# MainBoard.net
KiCad netlist of a schematic drawn in EAGLE
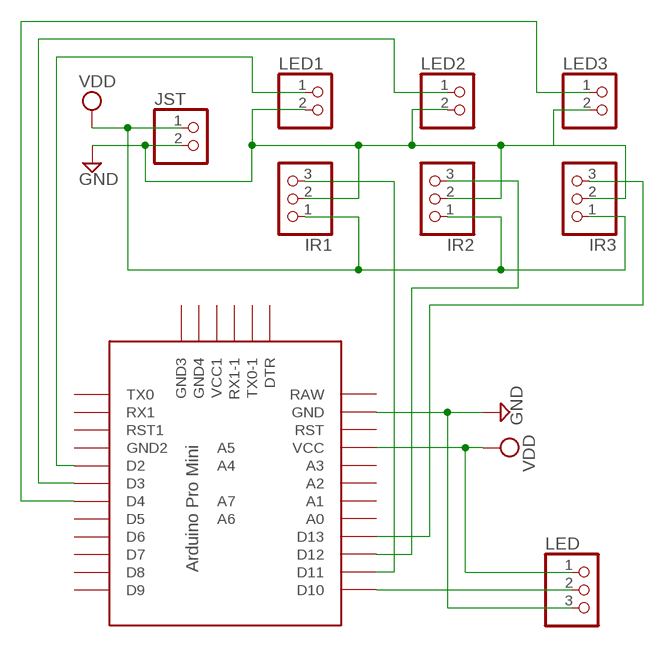
[diagram p0: schematic, sheet 1]

(export (version "E")
  (design (tool "Eeschema 10.0.6"))
  (components
    (comp (ref "IR1")
      (value "PINHD-1X3")
      (footprint "eagle-import:1X03")
      (libsource (lib "eagle-import") (part "PINHD-1X3"))
    )
    (comp (ref "IR2")
      (value "PINHD-1X3")
      (footprint "eagle-import:1X03")
      (libsource (lib "eagle-import") (part "PINHD-1X3"))
    )
    (comp (ref "IR3")
      (value "PINHD-1X3")
      (footprint "eagle-import:1X03")
      (libsource (lib "eagle-import") (part "PINHD-1X3"))
    )
    (comp (ref "JST")
      (value "PINHD-1X2/90")
      (footprint "eagle-import:1X02_90")
      (libsource (lib "eagle-import") (part "PINHD-1X2/90"))
    )
    (comp (ref "LED")
      (value "PINHD-1X3")
      (footprint "eagle-import:1X03")
      (libsource (lib "eagle-import") (part "PINHD-1X3"))
    )
    (comp (ref "LED1")
      (value "PINHD-1X2")
      (footprint "eagle-import:1X02")
      (libsource (lib "eagle-import") (part "PINHD-1X2"))
    )
    (comp (ref "LED2")
      (value "PINHD-1X2")
      (footprint "eagle-import:1X02")
      (libsource (lib "eagle-import") (part "PINHD-1X2"))
    )
    (comp (ref "LED3")
      (value "PINHD-1X2")
      (footprint "eagle-import:1X02")
      (libsource (lib "eagle-import") (part "PINHD-1X2"))
    )
    (comp (ref "U$1")
      (value "PRO-MINI-2")
      (footprint "eagle-import:PRO-MINI-2")
      (libsource (lib "eagle-import") (part "PRO-MINI-2"))
    )
  )
  (nets
    (net (code "1") (name "GND") (class "Default")
      (node (ref "IR1") (pin "2") (pinfunction "2_2") (pintype "passive"))
      (node (ref "IR2") (pin "2") (pinfunction "2_2") (pintype "passive"))
      (node (ref "IR3") (pin "2") (pinfunction "2_2") (pintype "passive"))
      (node (ref "JST") (pin "2") (pinfunction "2_2") (pintype "passive"))
      (node (ref "LED") (pin "3") (pinfunction "3_3") (pintype "passive"))
      (node (ref "LED1") (pin "2") (pinfunction "2_2") (pintype "passive"))
      (node (ref "LED2") (pin "2") (pinfunction "2_2") (pintype "passive"))
      (node (ref "LED3") (pin "2") (pinfunction "2_2") (pintype "passive"))
      (node (ref "U$1") (pin "GND") (pinfunction "GND_GND") (pintype "bidirectional"))
    )
    (net (code "2") (name "Net-(IR1-Pad3)") (class "Default")
      (node (ref "IR1") (pin "3") (pinfunction "3_3") (pintype "passive"))
      (node (ref "U$1") (pin "D11") (pinfunction "D11_D11") (pintype "bidirectional"))
    )
    (net (code "3") (name "Net-(IR2-Pad3)") (class "Default")
      (node (ref "IR2") (pin "3") (pinfunction "3_3") (pintype "passive"))
      (node (ref "U$1") (pin "D12") (pinfunction "D12_D12") (pintype "bidirectional"))
    )
    (net (code "4") (name "Net-(IR3-Pad3)") (class "Default")
      (node (ref "IR3") (pin "3") (pinfunction "3_3") (pintype "passive"))
      (node (ref "U$1") (pin "D13") (pinfunction "D13_D13") (pintype "bidirectional"))
    )
    (net (code "5") (name "Net-(LED-Pad2)") (class "Default")
      (node (ref "LED") (pin "2") (pinfunction "2_2") (pintype "passive"))
      (node (ref "U$1") (pin "D10") (pinfunction "D10_D10") (pintype "bidirectional"))
    )
    (net (code "6") (name "Net-(LED1-Pad1)") (class "Default")
      (node (ref "LED1") (pin "1") (pinfunction "1_1") (pintype "passive"))
      (node (ref "U$1") (pin "D2") (pinfunction "D2_D2") (pintype "bidirectional"))
    )
    (net (code "7") (name "Net-(LED2-Pad1)") (class "Default")
      (node (ref "LED2") (pin "1") (pinfunction "1_1") (pintype "passive"))
      (node (ref "U$1") (pin "D3") (pinfunction "D3_D3") (pintype "bidirectional"))
    )
    (net (code "8") (name "Net-(LED3-Pad1)") (class "Default")
      (node (ref "LED3") (pin "1") (pinfunction "1_1") (pintype "passive"))
      (node (ref "U$1") (pin "D4") (pinfunction "D4_D4") (pintype "bidirectional"))
    )
    (net (code "9") (name "VDD") (class "Default")
      (node (ref "IR1") (pin "1") (pinfunction "1_1") (pintype "passive"))
      (node (ref "IR2") (pin "1") (pinfunction "1_1") (pintype "passive"))
      (node (ref "IR3") (pin "1") (pinfunction "1_1") (pintype "passive"))
      (node (ref "JST") (pin "1") (pinfunction "1_1") (pintype "passive"))
      (node (ref "LED") (pin "1") (pinfunction "1_1") (pintype "passive"))
      (node (ref "U$1") (pin "VCC") (pinfunction "VCC_VCC") (pintype "bidirectional"))
    )
    (net (code "10") (name "unconnected-(U$1-GND2-PadGND1)") (class "Default")
      (node (ref "U$1") (pin "GND1") (pinfunction "GND2_GND1") (pintype "bidirectional"))
    )
    (net (code "11") (name "unconnected-(U$1-GND3-PadGND2)") (class "Default")
      (node (ref "U$1") (pin "GND2") (pinfunction "GND3_GND2") (pintype "bidirectional"))
    )
    (net (code "12") (name "unconnected-(U$1-GND4-PadGND3)") (class "Default")
      (node (ref "U$1") (pin "GND3") (pinfunction "GND4_GND3") (pintype "bidirectional"))
    )
    (net (code "13") (name "unconnected-(U$1-PadA0)") (class "Default")
      (node (ref "U$1") (pin "A0") (pinfunction "A0_A0") (pintype "bidirectional"))
    )
    (net (code "14") (name "unconnected-(U$1-PadA1)") (class "Default")
      (node (ref "U$1") (pin "A1") (pinfunction "A1_A1") (pintype "bidirectional"))
    )
    (net (code "15") (name "unconnected-(U$1-PadA2)") (class "Default")
      (node (ref "U$1") (pin "A2") (pinfunction "A2_A2") (pintype "bidirectional"))
    )
    (net (code "16") (name "unconnected-(U$1-PadA3)") (class "Default")
      (node (ref "U$1") (pin "A3") (pinfunction "A3_A3") (pintype "bidirectional"))
    )
    (net (code "17") (name "unconnected-(U$1-PadA4)") (class "Default")
      (node (ref "U$1") (pin "A4") (pinfunction "A4_A4") (pintype "bidirectional"))
    )
    (net (code "18") (name "unconnected-(U$1-PadA5)") (class "Default")
      (node (ref "U$1") (pin "A5") (pinfunction "A5_A5") (pintype "bidirectional"))
    )
    (net (code "19") (name "unconnected-(U$1-PadA6)") (class "Default")
      (node (ref "U$1") (pin "A6") (pinfunction "A6_A6") (pintype "bidirectional"))
    )
    (net (code "20") (name "unconnected-(U$1-PadA7)") (class "Default")
      (node (ref "U$1") (pin "A7") (pinfunction "A7_A7") (pintype "bidirectional"))
    )
    (net (code "21") (name "unconnected-(U$1-PadD5)") (class "Default")
      (node (ref "U$1") (pin "D5") (pinfunction "D5_D5") (pintype "bidirectional"))
    )
    (net (code "22") (name "unconnected-(U$1-PadD6)") (class "Default")
      (node (ref "U$1") (pin "D6") (pinfunction "D6_D6") (pintype "bidirectional"))
    )
    (net (code "23") (name "unconnected-(U$1-PadD7)") (class "Default")
      (node (ref "U$1") (pin "D7") (pinfunction "D7_D7") (pintype "bidirectional"))
    )
    (net (code "24") (name "unconnected-(U$1-PadD8)") (class "Default")
      (node (ref "U$1") (pin "D8") (pinfunction "D8_D8") (pintype "bidirectional"))
    )
    (net (code "25") (name "unconnected-(U$1-PadD9)") (class "Default")
      (node (ref "U$1") (pin "D9") (pinfunction "D9_D9") (pintype "bidirectional"))
    )
    (net (code "26") (name "unconnected-(U$1-PadDTR)") (class "Default")
      (node (ref "U$1") (pin "DTR") (pinfunction "DTR_DTR") (pintype "bidirectional"))
    )
    (net (code "27") (name "unconnected-(U$1-PadRAW)") (class "Default")
      (node (ref "U$1") (pin "RAW") (pinfunction "RAW_RAW") (pintype "bidirectional"))
    )
    (net (code "28") (name "unconnected-(U$1-PadRST)") (class "Default")
      (node (ref "U$1") (pin "RST") (pinfunction "RST_RST") (pintype "bidirectional"))
    )
    (net (code "29") (name "unconnected-(U$1-PadRST1)") (class "Default")
      (node (ref "U$1") (pin "RST1") (pinfunction "RST1_RST1") (pintype "bidirectional"))
    )
    (net (code "30") (name "unconnected-(U$1-PadRX1)") (class "Default")
      (node (ref "U$1") (pin "RX1") (pinfunction "RX1_RX1") (pintype "bidirectional"))
    )
    (net (code "31") (name "unconnected-(U$1-PadRX1-1)") (class "Default")
      (node (ref "U$1") (pin "RX1-1") (pinfunction "RX1-1_RX1-1") (pintype "bidirectional"))
    )
    (net (code "32") (name "unconnected-(U$1-PadTX0)") (class "Default")
      (node (ref "U$1") (pin "TX0") (pinfunction "TX0_TX0") (pintype "bidirectional"))
    )
    (net (code "33") (name "unconnected-(U$1-PadTX0-1)") (class "Default")
      (node (ref "U$1") (pin "TX0-1") (pinfunction "TX0-1_TX0-1") (pintype "bidirectional"))
    )
    (net (code "34") (name "unconnected-(U$1-PadVCC1)") (class "Default")
      (node (ref "U$1") (pin "VCC1") (pinfunction "VCC1_VCC1") (pintype "bidirectional"))
    )
  )
)
